# OZ440-SE140-CAR001_sheet5_enable_delay.net
KiCad netlist of a schematic drawn in Altium Designer
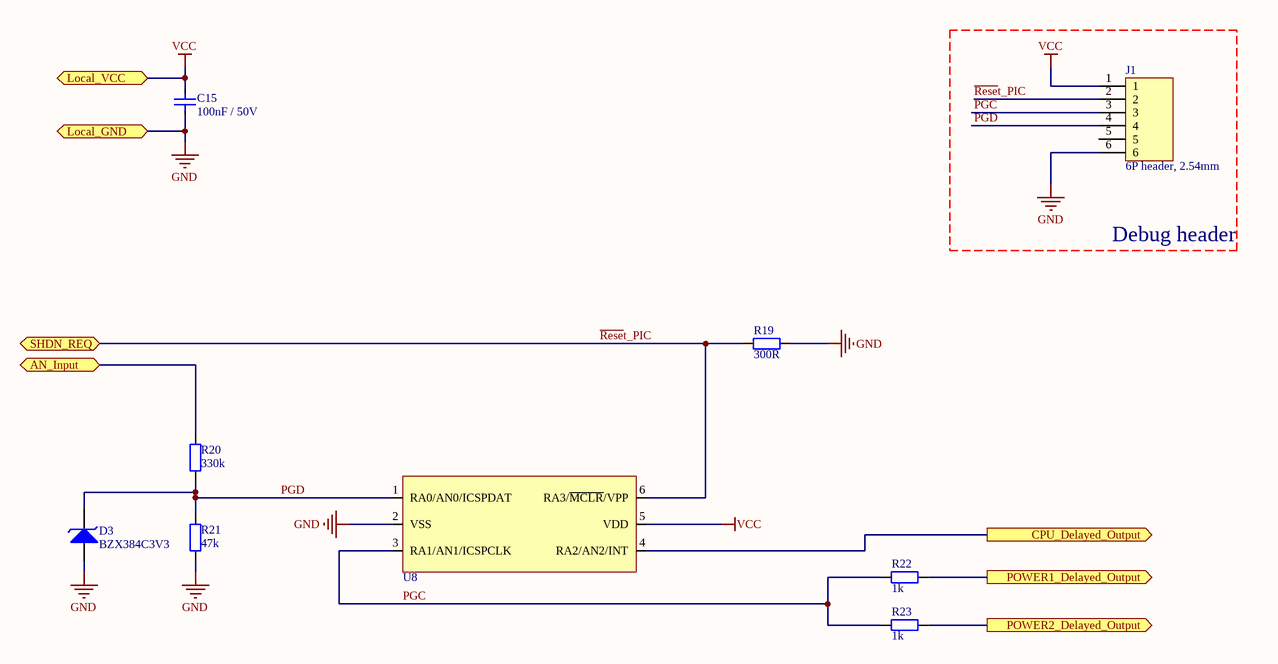
[diagram p0: OZ440-SE140-CAR001_sheet5_enable_delay.SchDoc]

(export (version "E")
  (design (tool "Eeschema 10.0.6"))
  (components
    (comp (ref "C15")
      (value "CAP-SMD")
      (footprint "C0805-STD")
      (description "0805 100nF / 50V  X7R ceramic capacitor")
      (fields
        (field (name "DISPLAYED REFERENCE") "100nF / 50V")
        (field (name "TOLERANCE") "+/- 10%")
        (field (name "MANUFACTURER") "vishay")
      )
      (libsource (lib "lib_NAIO") (part "CAP-SMD"))
    )
    (comp (ref "D3")
      (value "DIODE_ZENER-SOD323")
      (footprint "SOD323-SPE-BZX384")
      (description "3.3V zener diode")
      (fields (field (name "DISPLAYED REFERENCE") "BZX384C3V3") (field (name "MANUFACTURER") "VISHAY"))
      (libsource (lib "lib_NAIO") (part "DIODE_ZENER-SOD323"))
    )
    (comp (ref "J1")
      (value "CONN-STD-6P_1ROW")
      (footprint "6P_HEADER-STD_TH_1ROW")
      (description "6P, 1 row, 2.54mm header")
      (fields (field (name "DISPLAYED REFERENCE") "6P header, 2.54mm") (field (name "MANUFACTURER") "FCI"))
      (libsource (lib "lib_NAIO") (part "CONN-STD-6P_1ROW"))
    )
    (comp (ref "R19")
      (value "RES-SMD")
      (footprint "R0805-STD")
      (description "300 ohm 0805 SMD resistor")
      (fields
        (field (name "DISPLAYED REFERENCE") "300R")
        (field (name "TOLERANCE") "1%")
        (field (name "MANUFACTURER") "Vishay")
      )
      (libsource (lib "lib_NAIO") (part "RES-SMD"))
    )
    (comp (ref "R20")
      (value "RES-SMD")
      (footprint "R0805-STD")
      (description "330k Ohm 0805 SMD resistor")
      (fields
        (field (name "DISPLAYED REFERENCE") "330k")
        (field (name "TOLERANCE") "1%")
        (field (name "MANUFACTURER") "Vishay")
      )
      (libsource (lib "") (part "RES-SMD_1"))
    )
    (comp (ref "R21")
      (value "RES-SMD")
      (footprint "R0805-STD")
      (description "47k Ohm 0805 SMD resistor")
      (fields
        (field (name "DISPLAYED REFERENCE") "47k")
        (field (name "TOLERANCE") "1 %")
        (field (name "MANUFACTURER") "Vishay")
      )
      (libsource (lib "") (part "RES-SMD_2"))
    )
    (comp (ref "R22")
      (value "RES-SMD")
      (footprint "R0805-STD")
      (description "1k Ohm 0805 SMD resistor")
      (fields
        (field (name "DISPLAYED REFERENCE") "1k")
        (field (name "TOLERANCE") "1 %")
        (field (name "MANUFACTURER") "Vishay")
      )
      (libsource (lib "lib_NAIO") (part "RES-SMD"))
    )
    (comp (ref "R23")
      (value "RES-SMD")
      (footprint "R0805-STD")
      (description "1k Ohm 0805 SMD resistor")
      (fields
        (field (name "DISPLAYED REFERENCE") "1k")
        (field (name "TOLERANCE") "1 %")
        (field (name "MANUFACTURER") "Vishay")
      )
      (libsource (lib "lib_NAIO") (part "RES-SMD"))
    )
    (comp (ref "U8")
      (value "PIC10F320-SOT23_6")
      (footprint "SOT23_6-SPE-PIC10F320")
      (description "6 pin Low cost microcontroller")
      (fields (field (name "MANUFACTURER") "MICROCHIP"))
      (libsource (lib "lib_NAIO") (part "PIC10F320-SOT23_6"))
    )
  )
  (nets
    (net (code "1") (name "/AN_Input") (class "Default")
      (node (ref "R20") (pin "2") (pinfunction "2_2") (pintype "passive"))
    )
    (net (code "2") (name "/CPU_Delayed_Output") (class "Default")
      (node (ref "U8") (pin "4") (pinfunction "RA2/AN2/INT_4") (pintype "passive"))
    )
    (net (code "3") (name "/PGC") (class "Default")
      (node (ref "J1") (pin "3") (pinfunction "3_3") (pintype "passive"))
      (node (ref "R22") (pin "1") (pinfunction "1_1") (pintype "passive"))
      (node (ref "R23") (pin "1") (pinfunction "1_1") (pintype "passive"))
      (node (ref "U8") (pin "3") (pinfunction "RA1/AN1/ICSPCLK_3") (pintype "passive"))
    )
    (net (code "4") (name "/PGD") (class "Default")
      (node (ref "D3") (pin "K") (pinfunction "K_K") (pintype "passive"))
      (node (ref "J1") (pin "4") (pinfunction "4_4") (pintype "passive"))
      (node (ref "R20") (pin "1") (pinfunction "1_1") (pintype "passive"))
      (node (ref "R21") (pin "1") (pinfunction "1_1") (pintype "passive"))
      (node (ref "U8") (pin "1") (pinfunction "RA0/AN0/ICSPDAT_1") (pintype "passive"))
    )
    (net (code "5") (name "/POWER1_Delayed_Output") (class "Default")
      (node (ref "R22") (pin "2") (pinfunction "2_2") (pintype "passive"))
    )
    (net (code "6") (name "/POWER2_Delayed_Output") (class "Default")
      (node (ref "R23") (pin "2") (pinfunction "2_2") (pintype "passive"))
    )
    (net (code "7") (name "/~{Rese}t_PIC") (class "Default")
      (node (ref "J1") (pin "2") (pinfunction "2_2") (pintype "passive"))
      (node (ref "R19") (pin "1") (pinfunction "1_1") (pintype "passive"))
      (node (ref "U8") (pin "6") (pinfunction "RA3/~{MCLR}/VPP_6") (pintype "passive"))
    )
    (net (code "8") (name "GND") (class "Default")
      (node (ref "C15") (pin "2") (pinfunction "2_2") (pintype "passive"))
      (node (ref "D3") (pin "A") (pinfunction "A_A") (pintype "passive"))
      (node (ref "J1") (pin "6") (pinfunction "6_6") (pintype "passive"))
      (node (ref "R19") (pin "2") (pinfunction "2_2") (pintype "passive"))
      (node (ref "R21") (pin "2") (pinfunction "2_2") (pintype "passive"))
      (node (ref "U8") (pin "2") (pinfunction "VSS_2") (pintype "passive"))
    )
    (net (code "9") (name "VCC") (class "Default")
      (node (ref "C15") (pin "1") (pinfunction "1_1") (pintype "passive"))
      (node (ref "J1") (pin "1") (pinfunction "1_1") (pintype "passive"))
      (node (ref "U8") (pin "5") (pinfunction "VDD_5") (pintype "passive"))
    )
    (net (code "10") (name "unconnected-(J1-Pad5)") (class "Default")
      (node (ref "J1") (pin "5") (pinfunction "5_5") (pintype "passive"))
    )
  )
)
